# IMU.net
KiCad netlist of a schematic drawn in EAGLE
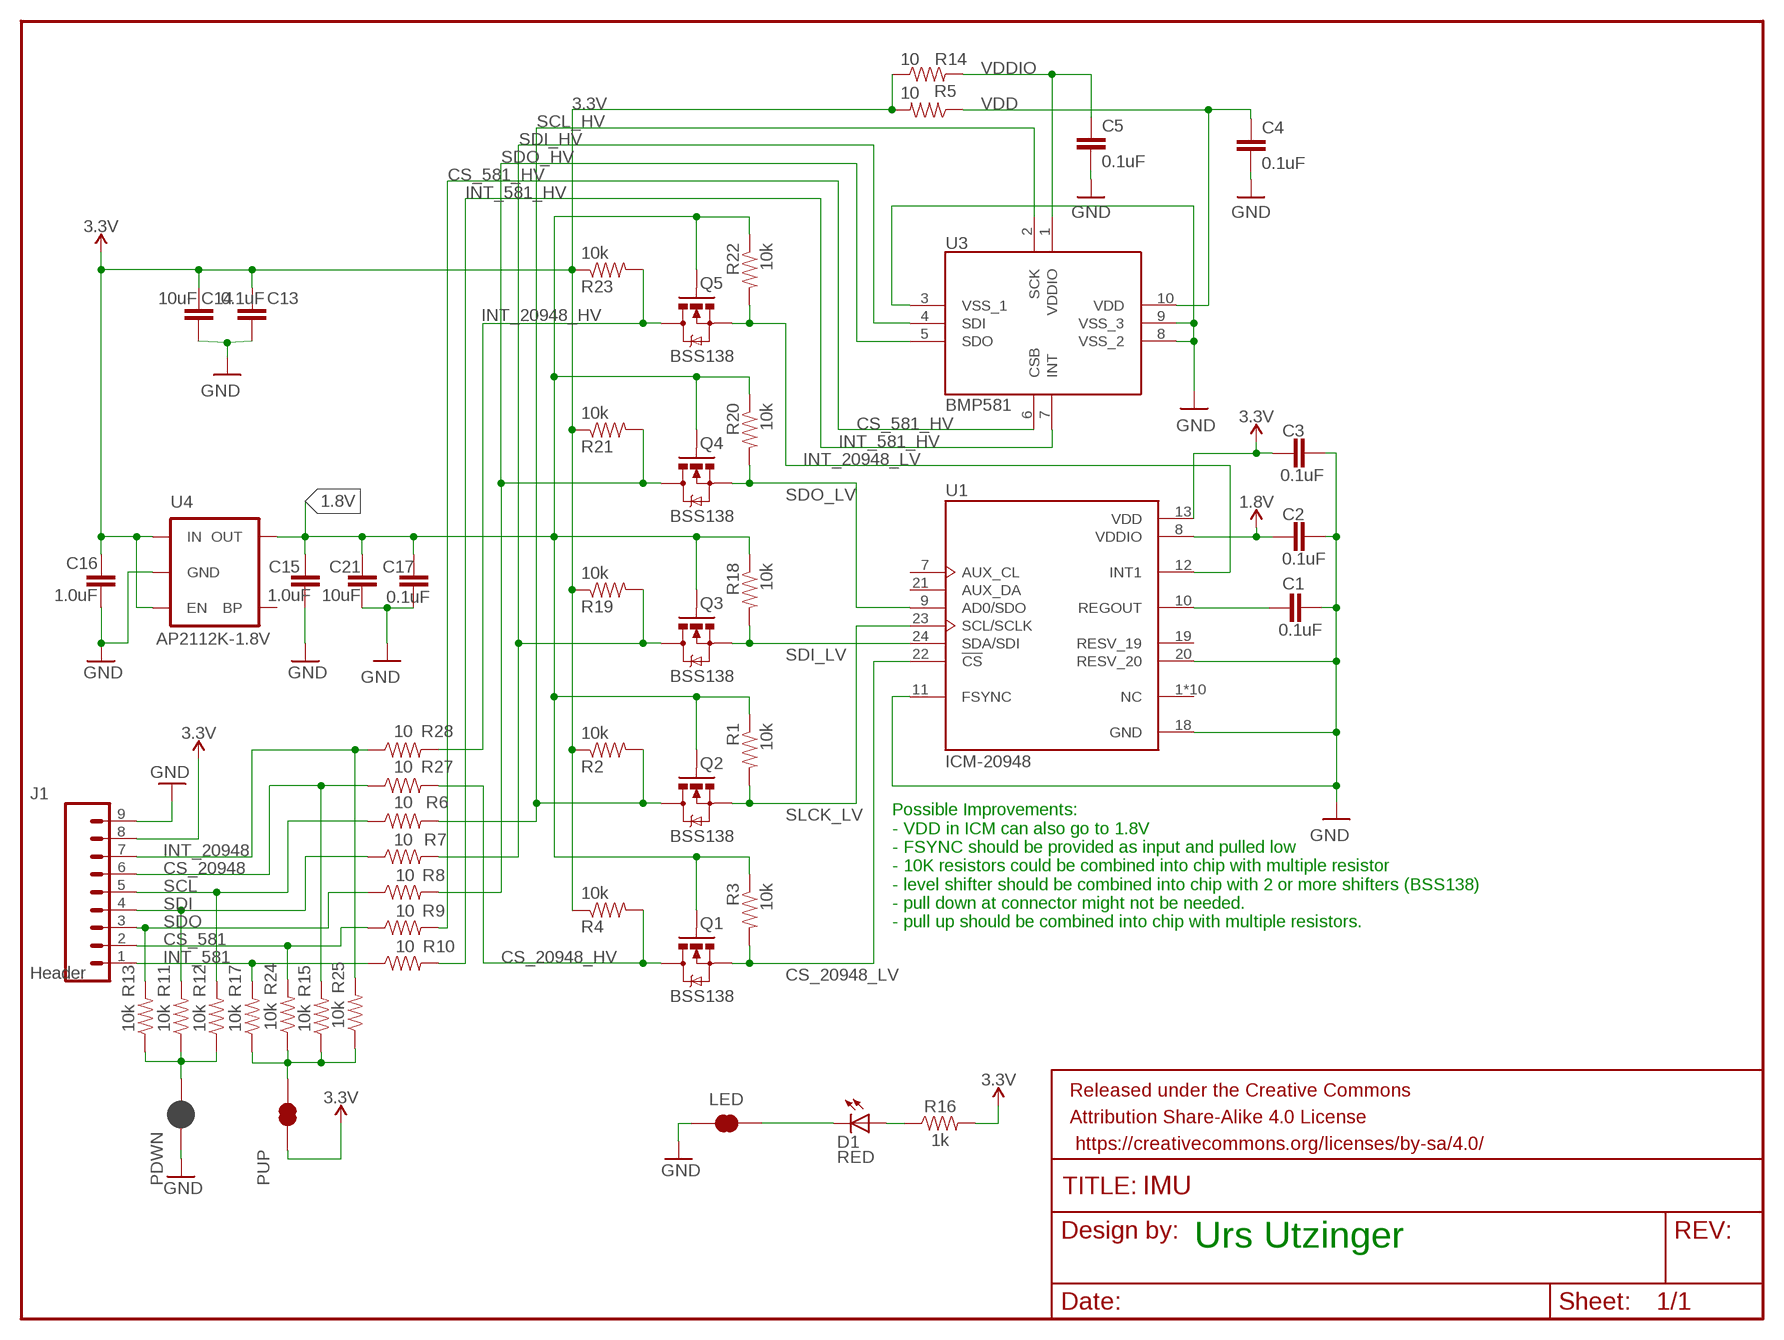
[diagram p0: schematic, sheet 1]

(export (version "E")
  (design (tool "Eeschema 10.0.6"))
  (components
    (comp (ref "C1")
      (value "0.1uF")
      (footprint "eagle-import:0603")
      (libsource (lib "eagle-import") (part "0.1UF-0603-25V-(+80/-20%)"))
    )
    (comp (ref "C2")
      (value "0.1uF")
      (footprint "eagle-import:0603")
      (libsource (lib "eagle-import") (part "0.1UF-0603-25V-(+80/-20%)"))
    )
    (comp (ref "C3")
      (value "0.1uF")
      (footprint "eagle-import:0603")
      (libsource (lib "eagle-import") (part "0.1UF-0603-25V-(+80/-20%)"))
    )
    (comp (ref "C4")
      (value "0.1uF")
      (footprint "eagle-import:0603")
      (libsource (lib "eagle-import") (part "0.1UF-0603-25V-(+80/-20%)"))
    )
    (comp (ref "C5")
      (value "0.1uF")
      (footprint "eagle-import:0603")
      (libsource (lib "eagle-import") (part "0.1UF-0603-25V-(+80/-20%)"))
    )
    (comp (ref "C13")
      (value "0.1uF")
      (footprint "eagle-import:0603")
      (libsource (lib "eagle-import") (part "0.1UF-0603-25V-(+80/-20%)"))
    )
    (comp (ref "C14")
      (value "10uF")
      (footprint "eagle-import:0603@1")
      (libsource (lib "eagle-import") (part "10UF-0603-6.3V-20%"))
    )
    (comp (ref "C15")
      (value "1.0uF")
      (footprint "eagle-import:0603")
      (libsource (lib "eagle-import") (part "1.0UF-0603-16V-10%"))
    )
    (comp (ref "C16")
      (value "1.0uF")
      (footprint "eagle-import:0603")
      (libsource (lib "eagle-import") (part "1.0UF-0603-16V-10%"))
    )
    (comp (ref "C17")
      (value "0.1uF")
      (footprint "eagle-import:0603")
      (libsource (lib "eagle-import") (part "0.1UF-0603-25V-(+80/-20%)"))
    )
    (comp (ref "C21")
      (value "10uF")
      (footprint "eagle-import:0603@1")
      (libsource (lib "eagle-import") (part "10UF-0603-6.3V-20%"))
    )
    (comp (ref "D1")
      (value "RED")
      (footprint "eagle-import:LED-0603")
      (libsource (lib "eagle-import") (part "LED-RED0603"))
    )
    (comp (ref "FRAME1")
      (value "FRAME-LETTERNO_PACKAGE")
      (footprint "eagle-import:DUMMY")
      (fields (field (name "DESIGNER") "Nobody"))
      (libsource (lib "eagle-import") (part "FRAME-LETTERNO_PACKAGE"))
    )
    (comp (ref "J1")
      (value "Header")
      (footprint "eagle-import:1X09")
      (libsource (lib "eagle-import") (part "CONN_09"))
    )
    (comp (ref "LED")
      (value "LED ENABLE")
      (footprint "eagle-import:SMT-JUMPER_2_NC_TRACE_SILK")
      (libsource (lib "eagle-import") (part "JUMPER-SMT_2_NC_TRACE_SILK"))
    )
    (comp (ref "PDWN")
      (value "JUMPER-SMT_2_NC_PASTE_SILK")
      (footprint "eagle-import:SMT-JUMPER_2_NC_PASTE_SILK")
      (libsource (lib "eagle-import") (part "JUMPER-SMT_2_NC_PASTE_SILK"))
    )
    (comp (ref "PUP")
      (value "JUMPER-SMT_2_NC_TRACE_SILK")
      (footprint "eagle-import:SMT-JUMPER_2_NC_TRACE_SILK")
      (libsource (lib "eagle-import") (part "JUMPER-SMT_2_NC_TRACE_SILK"))
    )
    (comp (ref "Q1")
      (value "BSS138")
      (footprint "eagle-import:SPARKFUN_SOT23-3")
      (libsource (lib "eagle-import") (part "SPARKFUN_MOSFET-NCHANNELSMD"))
    )
    (comp (ref "Q2")
      (value "BSS138")
      (footprint "eagle-import:SPARKFUN_SOT23-3")
      (libsource (lib "eagle-import") (part "SPARKFUN_MOSFET-NCHANNELSMD"))
    )
    (comp (ref "Q3")
      (value "BSS138")
      (footprint "eagle-import:SPARKFUN_SOT23-3")
      (libsource (lib "eagle-import") (part "SPARKFUN_MOSFET-NCHANNELSMD"))
    )
    (comp (ref "Q4")
      (value "BSS138")
      (footprint "eagle-import:SPARKFUN_SOT23-3")
      (libsource (lib "eagle-import") (part "SPARKFUN_MOSFET-NCHANNELSMD"))
    )
    (comp (ref "Q5")
      (value "BSS138")
      (footprint "eagle-import:SPARKFUN_SOT23-3")
      (libsource (lib "eagle-import") (part "SPARKFUN_MOSFET-NCHANNELSMD"))
    )
    (comp (ref "R1")
      (value "10k")
      (footprint "eagle-import:0603")
      (libsource (lib "eagle-import") (part "10KOHM-0603-1/10W-1%"))
    )
    (comp (ref "R2")
      (value "10k")
      (footprint "eagle-import:0603")
      (libsource (lib "eagle-import") (part "10KOHM-0603-1/10W-1%"))
    )
    (comp (ref "R3")
      (value "10k")
      (footprint "eagle-import:0603")
      (libsource (lib "eagle-import") (part "10KOHM-0603-1/10W-1%"))
    )
    (comp (ref "R4")
      (value "10k")
      (footprint "eagle-import:0603")
      (libsource (lib "eagle-import") (part "10KOHM-0603-1/10W-1%"))
    )
    (comp (ref "R5")
      (value "10")
      (footprint "eagle-import:0603")
      (libsource (lib "eagle-import") (part "10OHM-0603-1/10W-5%"))
    )
    (comp (ref "R6")
      (value "10")
      (footprint "eagle-import:0603")
      (libsource (lib "eagle-import") (part "10OHM-0603-1/10W-1%"))
    )
    (comp (ref "R7")
      (value "10")
      (footprint "eagle-import:0603")
      (libsource (lib "eagle-import") (part "10OHM-0603-1/10W-1%"))
    )
    (comp (ref "R8")
      (value "10")
      (footprint "eagle-import:0603")
      (libsource (lib "eagle-import") (part "10OHM-0603-1/10W-1%"))
    )
    (comp (ref "R9")
      (value "10")
      (footprint "eagle-import:0603")
      (libsource (lib "eagle-import") (part "10OHM-0603-1/10W-1%"))
    )
    (comp (ref "R10")
      (value "10")
      (footprint "eagle-import:0603")
      (libsource (lib "eagle-import") (part "10OHM-0603-1/10W-1%"))
    )
    (comp (ref "R11")
      (value "10k")
      (footprint "eagle-import:0603")
      (libsource (lib "eagle-import") (part "10KOHM-0603-1/10W-1%"))
    )
    (comp (ref "R12")
      (value "10k")
      (footprint "eagle-import:0603")
      (libsource (lib "eagle-import") (part "10KOHM-0603-1/10W-1%"))
    )
    (comp (ref "R13")
      (value "10k")
      (footprint "eagle-import:0603")
      (libsource (lib "eagle-import") (part "10KOHM-0603-1/10W-1%"))
    )
    (comp (ref "R14")
      (value "10")
      (footprint "eagle-import:0603")
      (libsource (lib "eagle-import") (part "10OHM-0603-1/10W-5%"))
    )
    (comp (ref "R15")
      (value "10k")
      (footprint "eagle-import:0603")
      (libsource (lib "eagle-import") (part "10KOHM-0603-1/10W-1%"))
    )
    (comp (ref "R16")
      (value "1k")
      (footprint "eagle-import:0603")
      (libsource (lib "eagle-import") (part "1KOHM-0603-1/10W-1%"))
    )
    (comp (ref "R17")
      (value "10k")
      (footprint "eagle-import:0603")
      (libsource (lib "eagle-import") (part "10KOHM-0603-1/10W-1%"))
    )
    (comp (ref "R18")
      (value "10k")
      (footprint "eagle-import:0603")
      (libsource (lib "eagle-import") (part "10KOHM-0603-1/10W-1%"))
    )
    (comp (ref "R19")
      (value "10k")
      (footprint "eagle-import:0603")
      (libsource (lib "eagle-import") (part "10KOHM-0603-1/10W-1%"))
    )
    (comp (ref "R20")
      (value "10k")
      (footprint "eagle-import:0603")
      (libsource (lib "eagle-import") (part "10KOHM-0603-1/10W-1%"))
    )
    (comp (ref "R21")
      (value "10k")
      (footprint "eagle-import:0603")
      (libsource (lib "eagle-import") (part "10KOHM-0603-1/10W-1%"))
    )
    (comp (ref "R22")
      (value "10k")
      (footprint "eagle-import:0603")
      (libsource (lib "eagle-import") (part "10KOHM-0603-1/10W-1%"))
    )
    (comp (ref "R23")
      (value "10k")
      (footprint "eagle-import:0603")
      (libsource (lib "eagle-import") (part "10KOHM-0603-1/10W-1%"))
    )
    (comp (ref "R24")
      (value "10k")
      (footprint "eagle-import:0603")
      (libsource (lib "eagle-import") (part "10KOHM-0603-1/10W-1%"))
    )
    (comp (ref "R25")
      (value "10k")
      (footprint "eagle-import:0603")
      (libsource (lib "eagle-import") (part "10KOHM-0603-1/10W-1%"))
    )
    (comp (ref "R27")
      (value "10")
      (footprint "eagle-import:0603")
      (libsource (lib "eagle-import") (part "10OHM-0603-1/10W-1%"))
    )
    (comp (ref "R28")
      (value "10")
      (footprint "eagle-import:0603")
      (libsource (lib "eagle-import") (part "10OHM-0603-1/10W-1%"))
    )
    (comp (ref "U1")
      (value "ICM-20948")
      (footprint "eagle-import:QFN40P300X300X105-24N")
      (fields (field (name "MANUFACTURER") "TDK InvenSense"))
      (libsource (lib "eagle-import") (part "ICM-20948"))
    )
    (comp (ref "U3")
      (value "BMP581")
      (footprint "eagle-import:BMP581")
      (fields (field (name "MOUSER_PART_NUMBER") "262-BMP581"))
      (libsource (lib "eagle-import") (part "BMP581"))
    )
    (comp (ref "U4")
      (value "AP2112K-1.8V")
      (footprint "eagle-import:SPARKFUN-POWERIC_SOT23-5")
      (libsource (lib "eagle-import") (part "AP2122K-1.8TRG1SMD"))
    )
  )
  (nets
    (net (code "1") (name "/CS_581") (class "Default")
      (node (ref "J1") (pin "2") (pinfunction "2_2") (pintype "passive"))
      (node (ref "R24") (pin "2") (pinfunction "2_2") (pintype "passive"))
      (node (ref "R9") (pin "1") (pinfunction "1_1") (pintype "passive"))
    )
    (net (code "2") (name "/CS_581_HV") (class "Default")
      (node (ref "R9") (pin "2") (pinfunction "2_2") (pintype "passive"))
      (node (ref "U3") (pin "6") (pinfunction "CSB_6") (pintype "bidirectional"))
    )
    (net (code "3") (name "/CS_20948") (class "Default")
      (node (ref "J1") (pin "6") (pinfunction "6_6") (pintype "passive"))
      (node (ref "R15") (pin "2") (pinfunction "2_2") (pintype "passive"))
      (node (ref "R27") (pin "1") (pinfunction "1_1") (pintype "passive"))
    )
    (net (code "4") (name "/CS_20948_HV") (class "Default")
      (node (ref "Q1") (pin "3") (pinfunction "D_3") (pintype "passive"))
      (node (ref "R27") (pin "2") (pinfunction "2_2") (pintype "passive"))
      (node (ref "R4") (pin "2") (pinfunction "2_2") (pintype "passive"))
    )
    (net (code "5") (name "/CS_20948_LV") (class "Default")
      (node (ref "Q1") (pin "2") (pinfunction "S_2") (pintype "passive"))
      (node (ref "R3") (pin "2") (pinfunction "2_2") (pintype "passive"))
      (node (ref "U1") (pin "22") (pinfunction "~{CS}_22") (pintype "input"))
    )
    (net (code "6") (name "/INT_581") (class "Default")
      (node (ref "J1") (pin "1") (pinfunction "1_1") (pintype "passive"))
      (node (ref "R10") (pin "1") (pinfunction "1_1") (pintype "passive"))
      (node (ref "R17") (pin "2") (pinfunction "2_2") (pintype "passive"))
    )
    (net (code "7") (name "/INT_581_HV") (class "Default")
      (node (ref "R10") (pin "2") (pinfunction "2_2") (pintype "passive"))
      (node (ref "U3") (pin "7") (pinfunction "INT_7") (pintype "bidirectional"))
    )
    (net (code "8") (name "/INT_20948") (class "Default")
      (node (ref "J1") (pin "7") (pinfunction "7_7") (pintype "passive"))
      (node (ref "R25") (pin "2") (pinfunction "2_2") (pintype "passive"))
      (node (ref "R28") (pin "1") (pinfunction "1_1") (pintype "passive"))
    )
    (net (code "9") (name "/INT_20948_HV") (class "Default")
      (node (ref "Q5") (pin "3") (pinfunction "D_3") (pintype "passive"))
      (node (ref "R23") (pin "2") (pinfunction "2_2") (pintype "passive"))
      (node (ref "R28") (pin "2") (pinfunction "2_2") (pintype "passive"))
    )
    (net (code "10") (name "/INT_20948_LV") (class "Default")
      (node (ref "Q5") (pin "2") (pinfunction "S_2") (pintype "passive"))
      (node (ref "R22") (pin "2") (pinfunction "2_2") (pintype "passive"))
      (node (ref "U1") (pin "12") (pinfunction "INT1_12") (pintype "output"))
    )
    (net (code "11") (name "/SCL") (class "Default")
      (node (ref "J1") (pin "5") (pinfunction "5_5") (pintype "passive"))
      (node (ref "R12") (pin "2") (pinfunction "2_2") (pintype "passive"))
      (node (ref "R6") (pin "1") (pinfunction "1_1") (pintype "passive"))
    )
    (net (code "12") (name "/SCL_HV") (class "Default")
      (node (ref "Q2") (pin "3") (pinfunction "D_3") (pintype "passive"))
      (node (ref "R2") (pin "2") (pinfunction "2_2") (pintype "passive"))
      (node (ref "R6") (pin "2") (pinfunction "2_2") (pintype "passive"))
      (node (ref "U3") (pin "2") (pinfunction "SCK_2") (pintype "bidirectional"))
    )
    (net (code "13") (name "/SDI") (class "Default")
      (node (ref "J1") (pin "4") (pinfunction "4_4") (pintype "passive"))
      (node (ref "R11") (pin "2") (pinfunction "2_2") (pintype "passive"))
      (node (ref "R7") (pin "1") (pinfunction "1_1") (pintype "passive"))
    )
    (net (code "14") (name "/SDI_HV") (class "Default")
      (node (ref "Q3") (pin "3") (pinfunction "D_3") (pintype "passive"))
      (node (ref "R19") (pin "2") (pinfunction "2_2") (pintype "passive"))
      (node (ref "R7") (pin "2") (pinfunction "2_2") (pintype "passive"))
      (node (ref "U3") (pin "4") (pinfunction "SDI_4") (pintype "bidirectional"))
    )
    (net (code "15") (name "/SDI_LV") (class "Default")
      (node (ref "Q3") (pin "2") (pinfunction "S_2") (pintype "passive"))
      (node (ref "R18") (pin "2") (pinfunction "2_2") (pintype "passive"))
      (node (ref "U1") (pin "24") (pinfunction "SDA/SDI_24") (pintype "bidirectional"))
    )
    (net (code "16") (name "/SDO") (class "Default")
      (node (ref "J1") (pin "3") (pinfunction "3_3") (pintype "passive"))
      (node (ref "R13") (pin "2") (pinfunction "2_2") (pintype "passive"))
      (node (ref "R8") (pin "1") (pinfunction "1_1") (pintype "passive"))
    )
    (net (code "17") (name "/SDO_HV") (class "Default")
      (node (ref "Q4") (pin "3") (pinfunction "D_3") (pintype "passive"))
      (node (ref "R21") (pin "2") (pinfunction "2_2") (pintype "passive"))
      (node (ref "R8") (pin "2") (pinfunction "2_2") (pintype "passive"))
      (node (ref "U3") (pin "5") (pinfunction "SDO_5") (pintype "bidirectional"))
    )
    (net (code "18") (name "/SDO_LV") (class "Default")
      (node (ref "Q4") (pin "2") (pinfunction "S_2") (pintype "passive"))
      (node (ref "R20") (pin "2") (pinfunction "2_2") (pintype "passive"))
      (node (ref "U1") (pin "9") (pinfunction "AD0/SDO_9") (pintype "bidirectional"))
    )
    (net (code "19") (name "/SLCK_LV") (class "Default")
      (node (ref "Q2") (pin "2") (pinfunction "S_2") (pintype "passive"))
      (node (ref "R1") (pin "2") (pinfunction "2_2") (pintype "passive"))
      (node (ref "U1") (pin "23") (pinfunction "SCL/SCLK_23") (pintype "input"))
    )
    (net (code "20") (name "/VDD") (class "Default")
      (node (ref "C4") (pin "1") (pinfunction "1_1") (pintype "passive"))
      (node (ref "R5") (pin "1") (pinfunction "1_1") (pintype "passive"))
      (node (ref "U3") (pin "10") (pinfunction "VDD_10") (pintype "bidirectional"))
    )
    (net (code "21") (name "/VDDIO") (class "Default")
      (node (ref "C5") (pin "1") (pinfunction "1_1") (pintype "passive"))
      (node (ref "R14") (pin "2") (pinfunction "2_2") (pintype "passive"))
      (node (ref "U3") (pin "1") (pinfunction "VDDIO_1") (pintype "bidirectional"))
    )
    (net (code "22") (name "1.8V") (class "Default")
      (node (ref "C15") (pin "2") (pinfunction "2_2") (pintype "passive"))
      (node (ref "C17") (pin "1") (pinfunction "1_1") (pintype "passive"))
      (node (ref "C2") (pin "1") (pinfunction "1_1") (pintype "passive"))
      (node (ref "C21") (pin "1") (pinfunction "1_1") (pintype "passive"))
      (node (ref "Q1") (pin "1") (pinfunction "G_1") (pintype "passive"))
      (node (ref "Q2") (pin "1") (pinfunction "G_1") (pintype "passive"))
      (node (ref "Q3") (pin "1") (pinfunction "G_1") (pintype "passive"))
      (node (ref "Q4") (pin "1") (pinfunction "G_1") (pintype "passive"))
      (node (ref "Q5") (pin "1") (pinfunction "G_1") (pintype "passive"))
      (node (ref "R1") (pin "1") (pinfunction "1_1") (pintype "passive"))
      (node (ref "R18") (pin "1") (pinfunction "1_1") (pintype "passive"))
      (node (ref "R20") (pin "1") (pinfunction "1_1") (pintype "passive"))
      (node (ref "R22") (pin "1") (pinfunction "1_1") (pintype "passive"))
      (node (ref "R3") (pin "1") (pinfunction "1_1") (pintype "passive"))
      (node (ref "U1") (pin "8") (pinfunction "VDDIO_8") (pintype "power_in"))
      (node (ref "U4") (pin "5") (pinfunction "OUT_5") (pintype "passive"))
    )
    (net (code "23") (name "3.3V") (class "Default")
      (node (ref "C13") (pin "1") (pinfunction "1_1") (pintype "passive"))
      (node (ref "C14") (pin "1") (pinfunction "1_1") (pintype "passive"))
      (node (ref "C16") (pin "2") (pinfunction "2_2") (pintype "passive"))
      (node (ref "C3") (pin "1") (pinfunction "1_1") (pintype "passive"))
      (node (ref "J1") (pin "8") (pinfunction "8_8") (pintype "passive"))
      (node (ref "PUP") (pin "1") (pinfunction "1_1") (pintype "passive"))
      (node (ref "R14") (pin "1") (pinfunction "1_1") (pintype "passive"))
      (node (ref "R16") (pin "2") (pinfunction "2_2") (pintype "passive"))
      (node (ref "R19") (pin "1") (pinfunction "1_1") (pintype "passive"))
      (node (ref "R2") (pin "1") (pinfunction "1_1") (pintype "passive"))
      (node (ref "R21") (pin "1") (pinfunction "1_1") (pintype "passive"))
      (node (ref "R23") (pin "1") (pinfunction "1_1") (pintype "passive"))
      (node (ref "R4") (pin "1") (pinfunction "1_1") (pintype "passive"))
      (node (ref "R5") (pin "2") (pinfunction "2_2") (pintype "passive"))
      (node (ref "U1") (pin "13") (pinfunction "VDD_13") (pintype "power_in"))
      (node (ref "U4") (pin "1") (pinfunction "IN_1") (pintype "input"))
      (node (ref "U4") (pin "3") (pinfunction "EN_3") (pintype "input"))
    )
    (net (code "24") (name "GND") (class "Default")
      (node (ref "C1") (pin "2") (pinfunction "2_2") (pintype "passive"))
      (node (ref "C13") (pin "2") (pinfunction "2_2") (pintype "passive"))
      (node (ref "C14") (pin "2") (pinfunction "2_2") (pintype "passive"))
      (node (ref "C15") (pin "1") (pinfunction "1_1") (pintype "passive"))
      (node (ref "C16") (pin "1") (pinfunction "1_1") (pintype "passive"))
      (node (ref "C17") (pin "2") (pinfunction "2_2") (pintype "passive"))
      (node (ref "C2") (pin "2") (pinfunction "2_2") (pintype "passive"))
      (node (ref "C21") (pin "2") (pinfunction "2_2") (pintype "passive"))
      (node (ref "C3") (pin "2") (pinfunction "2_2") (pintype "passive"))
      (node (ref "C4") (pin "2") (pinfunction "2_2") (pintype "passive"))
      (node (ref "C5") (pin "2") (pinfunction "2_2") (pintype "passive"))
      (node (ref "J1") (pin "9") (pinfunction "9_9") (pintype "passive"))
      (node (ref "LED") (pin "1") (pinfunction "1_1") (pintype "passive"))
      (node (ref "PDWN") (pin "1") (pinfunction "1_1") (pintype "passive"))
      (node (ref "U1") (pin "11") (pinfunction "FSYNC_11") (pintype "input"))
      (node (ref "U1") (pin "18") (pinfunction "GND_18") (pintype "power_in"))
      (node (ref "U1") (pin "20") (pinfunction "RESV_20_20") (pintype "passive"))
      (node (ref "U3") (pin "3") (pinfunction "VSS_1_3") (pintype "bidirectional"))
      (node (ref "U3") (pin "8") (pinfunction "VSS_2_8") (pintype "bidirectional"))
      (node (ref "U3") (pin "9") (pinfunction "VSS_3_9") (pintype "bidirectional"))
      (node (ref "U4") (pin "2") (pinfunction "GND_2") (pintype "input"))
    )
    (net (code "25") (name "Net-(D1-PadA)") (class "Default")
      (node (ref "D1") (pin "A") (pinfunction "A_A") (pintype "passive"))
      (node (ref "R16") (pin "1") (pinfunction "1_1") (pintype "passive"))
    )
    (net (code "26") (name "Net-(D1-PadC)") (class "Default")
      (node (ref "D1") (pin "C") (pinfunction "C_C") (pintype "passive"))
      (node (ref "LED") (pin "2") (pinfunction "2_2") (pintype "passive"))
    )
    (net (code "27") (name "Net-(PDWN-Pad2)") (class "Default")
      (node (ref "PDWN") (pin "2") (pinfunction "2_2") (pintype "passive"))
      (node (ref "R11") (pin "1") (pinfunction "1_1") (pintype "passive"))
      (node (ref "R12") (pin "1") (pinfunction "1_1") (pintype "passive"))
      (node (ref "R13") (pin "1") (pinfunction "1_1") (pintype "passive"))
    )
    (net (code "28") (name "Net-(PUP-Pad2)") (class "Default")
      (node (ref "PUP") (pin "2") (pinfunction "2_2") (pintype "passive"))
      (node (ref "R15") (pin "1") (pinfunction "1_1") (pintype "passive"))
      (node (ref "R17") (pin "1") (pinfunction "1_1") (pintype "passive"))
      (node (ref "R24") (pin "1") (pinfunction "1_1") (pintype "passive"))
      (node (ref "R25") (pin "1") (pinfunction "1_1") (pintype "passive"))
    )
    (net (code "29") (name "Net-(U1-REGOUT)") (class "Default")
      (node (ref "C1") (pin "1") (pinfunction "1_1") (pintype "passive"))
      (node (ref "U1") (pin "10") (pinfunction "REGOUT_10") (pintype "output"))
    )
    (net (code "30") (name "unconnected-(U1-AUX_CL-Pad7)") (class "Default")
      (node (ref "U1") (pin "7") (pinfunction "AUX_CL_7") (pintype "input"))
    )
    (net (code "31") (name "unconnected-(U1-AUX_DA-Pad21)") (class "Default")
      (node (ref "U1") (pin "21") (pinfunction "AUX_DA_21") (pintype "bidirectional"))
    )
    (net (code "32") (name "unconnected-(U1-NC-Pad1)") (class "Default")
      (node (ref "U1") (pin "1") (pinfunction "NC_1") (pintype "no_connect"))
    )
    (net (code "33") (name "unconnected-(U1-NC-Pad2)") (class "Default")
      (node (ref "U1") (pin "2") (pinfunction "NC_2") (pintype "no_connect"))
    )
    (net (code "34") (name "unconnected-(U1-NC-Pad3)") (class "Default")
      (node (ref "U1") (pin "3") (pinfunction "NC_3") (pintype "no_connect"))
    )
    (net (code "35") (name "unconnected-(U1-NC-Pad4)") (class "Default")
      (node (ref "U1") (pin "4") (pinfunction "NC_4") (pintype "no_connect"))
    )
    (net (code "36") (name "unconnected-(U1-NC-Pad5)") (class "Default")
      (node (ref "U1") (pin "5") (pinfunction "NC_5") (pintype "no_connect"))
    )
    (net (code "37") (name "unconnected-(U1-NC-Pad6)") (class "Default")
      (node (ref "U1") (pin "6") (pinfunction "NC_6") (pintype "no_connect"))
    )
    (net (code "38") (name "unconnected-(U1-NC-Pad14)") (class "Default")
      (node (ref "U1") (pin "14") (pinfunction "NC_14") (pintype "no_connect"))
    )
    (net (code "39") (name "unconnected-(U1-NC-Pad15)") (class "Default")
      (node (ref "U1") (pin "15") (pinfunction "NC_15") (pintype "no_connect"))
    )
    (net (code "40") (name "unconnected-(U1-NC-Pad16)") (class "Default")
      (node (ref "U1") (pin "16") (pinfunction "NC_16") (pintype "no_connect"))
    )
    (net (code "41") (name "unconnected-(U1-NC-Pad17)") (class "Default")
      (node (ref "U1") (pin "17") (pinfunction "NC_17") (pintype "no_connect"))
    )
    (net (code "42") (name "unconnected-(U1-RESV_19-Pad19)") (class "Default")
      (node (ref "U1") (pin "19") (pinfunction "RESV_19_19") (pintype "passive"))
    )
    (net (code "43") (name "unconnected-(U4-BP-Pad4)") (class "Default")
      (node (ref "U4") (pin "4") (pinfunction "BP_4") (pintype "input"))
    )
  )
)
